# LM-008.net
KiCad netlist of a schematic drawn in Altium Designer
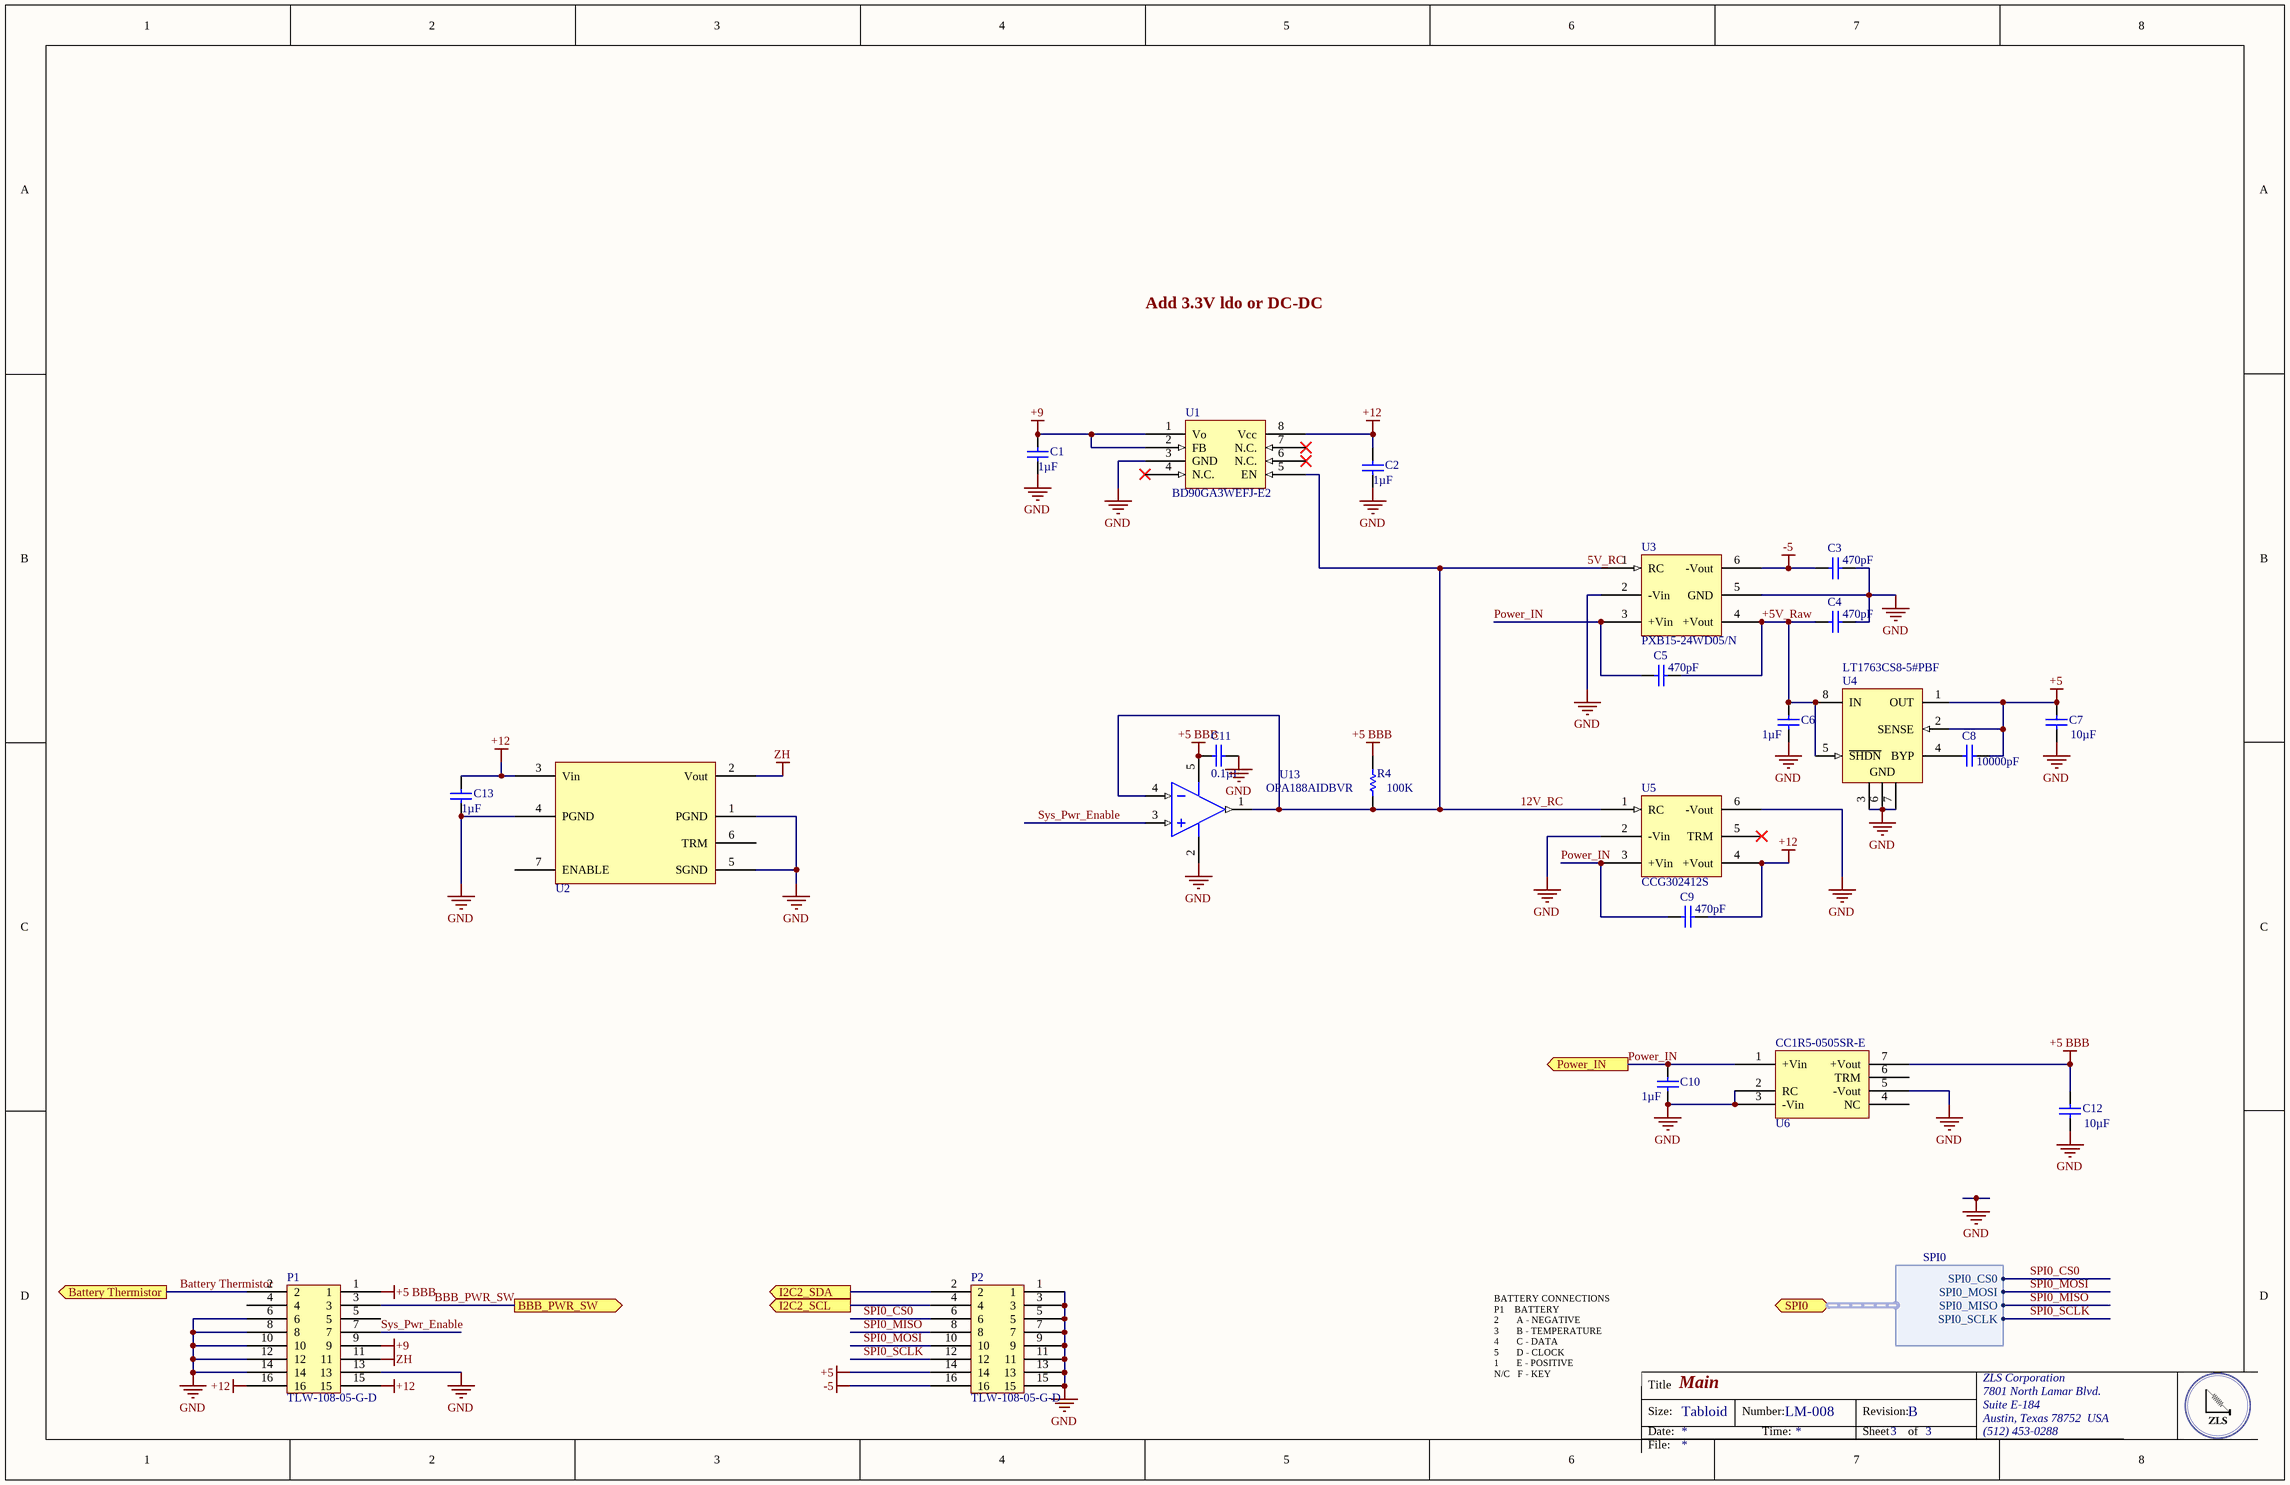
[diagram p0: LM-008.SchDoc]

(export (version "E")
  (design (tool "Eeschema 10.0.6"))
  (components
    (comp (ref "C1")
      (value "CAP CER 1UF 50V X7R 1210")
      (footprint "CAPC1206(3216)130_N")
      (fields
        (field (name "MANUFACTURER") "Murata Electronics North America")
        (field (name "MANUFACTURER PART NUMBER") "GRM32RR71H105KA01L")
        (field (name "CAPACITANCE") "1µF")
        (field (name "TOLERANCE") "±10%")
      )
      (libsource (lib "Altium Content Vault") (part "CMP-1037-04913-1"))
    )
    (comp (ref "C2")
      (value "CAP CER 1UF 50V X7R 1210")
      (footprint "CAPC1206(3216)130_N")
      (fields
        (field (name "MANUFACTURER") "Murata Electronics North America")
        (field (name "MANUFACTURER PART NUMBER") "GRM32RR71H105KA01L")
        (field (name "CAPACITANCE") "1µF")
        (field (name "TOLERANCE") "±10%")
      )
      (libsource (lib "Altium Content Vault") (part "CMP-1037-04913-1"))
    )
    (comp (ref "C3")
      (value "CAP CER 470PF 3KV X7R 1812")
      (footprint "CAPC1812(4532)230_M")
      (fields
        (field (name "MANUFACTURER") "Kemet")
        (field (name "MANUFACTURER PART NUMBER") "C1812C471KHRACTU")
        (field (name "CAPACITANCE") "470pF")
        (field (name "TOLERANCE") "10%")
      )
      (libsource (lib "Altium Content Vault") (part "CMP-1040-00561-1"))
    )
    (comp (ref "C4")
      (value "CAP CER 470PF 3KV X7R 1812")
      (footprint "CAPC1812(4532)230_M")
      (fields
        (field (name "MANUFACTURER") "Kemet")
        (field (name "MANUFACTURER PART NUMBER") "C1812C471KHRACTU")
        (field (name "CAPACITANCE") "470pF")
        (field (name "TOLERANCE") "10%")
      )
      (libsource (lib "Altium Content Vault") (part "CMP-1040-00561-1"))
    )
    (comp (ref "C5")
      (value "CAP CER 470PF 3KV X7R 1812")
      (footprint "CAPC1812(4532)230_M")
      (fields
        (field (name "MANUFACTURER") "Kemet")
        (field (name "MANUFACTURER PART NUMBER") "C1812C471KHRACTU")
        (field (name "CAPACITANCE") "470pF")
        (field (name "TOLERANCE") "10%")
      )
      (libsource (lib "Altium Content Vault") (part "CMP-1040-00561-1"))
    )
    (comp (ref "C6")
      (value "CAP CER 1UF 50V X7R 1210")
      (footprint "CAPC1210(3225)100_L")
      (fields
        (field (name "MANUFACTURER") "Murata Electronics North America")
        (field (name "MANUFACTURER PART NUMBER") "GRM32RR71H105KA01L")
        (field (name "CAPACITANCE") "1µF")
        (field (name "TOLERANCE") "±10%")
      )
      (libsource (lib "Altium Content Vault") (part "CMP-1038-00632-1"))
    )
    (comp (ref "C7")
      (value "CAP CER 10UF 10V X7R 0805")
      (footprint "CAPC0805(2012)145_N")
      (fields
        (field (name "MANUFACTURER") "Murata Electronics North America")
        (field (name "MANUFACTURER PART NUMBER") "GCM21BR71A106KE22L")
        (field (name "CAPACITANCE") "10µF")
        (field (name "TOLERANCE") "±10%")
      )
      (libsource (lib "Altium Content Vault") (part "CMP-1036-04795-1"))
    )
    (comp (ref "C8")
      (value "CAP CER 10000PF 25V X7R 0805")
      (footprint "CAPC0805(2012)145_N")
      (fields
        (field (name "MANUFACTURER") "Murata Electronics North America")
        (field (name "MANUFACTURER PART NUMBER") "GRM216R71E103KA01D")
        (field (name "CAPACITANCE") "10000pF")
        (field (name "TOLERANCE") "±10%")
      )
      (libsource (lib "Altium Content Vault") (part "CMP-1036-04795-1"))
    )
    (comp (ref "C9")
      (value "CAP CER 470PF 3KV X7R 1812")
      (footprint "CAPC1812(4532)230_M")
      (fields
        (field (name "MANUFACTURER") "Kemet")
        (field (name "MANUFACTURER PART NUMBER") "C1812C471KHRACTU")
        (field (name "CAPACITANCE") "470pF")
        (field (name "TOLERANCE") "10%")
      )
      (libsource (lib "Altium Content Vault") (part "CMP-1040-00561-1"))
    )
    (comp (ref "C10")
      (value "CAP CER 1UF 50V X7R 1210")
      (footprint "CAPC1210(3225)100_L")
      (fields
        (field (name "MANUFACTURER") "Murata Electronics North America")
        (field (name "MANUFACTURER PART NUMBER") "GRM32RR71H105KA01L")
        (field (name "CAPACITANCE") "1µF")
        (field (name "TOLERANCE") "±10%")
      )
      (libsource (lib "Altium Content Vault") (part "CMP-1038-00632-1"))
    )
    (comp (ref "C11")
      (value "CAP CER 0.1UF 16V X7R 0805")
      (footprint "CAPC0805(2012)145_N")
      (fields
        (field (name "TOLERANCE") "±10%")
        (field (name "MANUFACTURER") "Murata Electronics North America")
        (field (name "MANUFACTURER PART NUMBER") "GRM219R71C104KA01D")
        (field (name "CAPACITANCE") "0.1µF")
      )
      (libsource (lib "Altium Content Vault") (part "CMP-1036-04795-1"))
    )
    (comp (ref "C12")
      (value "CAP CER 10UF 10V X7R 0805")
      (footprint "CAPC0805(2012)145_N")
      (fields
        (field (name "MANUFACTURER") "Murata Electronics North America")
        (field (name "MANUFACTURER PART NUMBER") "GCM21BR71A106KE22L")
        (field (name "CAPACITANCE") "10µF")
        (field (name "TOLERANCE") "±10%")
      )
      (libsource (lib "Altium Content Vault") (part "CMP-1036-04795-1"))
    )
    (comp (ref "C13")
      (value "CAP CER 1UF 16V X7R 0805")
      (footprint "CAPC0805(2012)145_N")
      (fields
        (field (name "MANUFACTURER") "Taiyo Yuden")
        (field (name "MANUFACTURER PART NUMBER") "EMK212B7105KG-T")
        (field (name "CAPACITANCE") "1µF")
        (field (name "TOLERANCE") "±10%")
      )
      (libsource (lib "Altium Content Vault") (part "CMP-1036-04795-1"))
    )
    (comp (ref "P1")
      (value "TLW-108-05-G-D")
      (footprint "TLW-108-05-G-D")
      (description "CONN HEADER .100\" 16POS DL GOLD")
      (fields
        (field (name "MANUFACTURER") "Samtec Inc.")
        (field (name "MANUFACTURER PART NUMBER") "TLW-108-05-G-D")
      )
      (libsource (lib "ZLS_Schematic_lib") (part "TLW-108-05-G-D"))
    )
    (comp (ref "P2")
      (value "TLW-108-05-G-D")
      (footprint "TLW-108-05-G-D")
      (description "CONN HEADER .100\" 16POS DL GOLD")
      (fields
        (field (name "MANUFACTURER") "Samtec Inc.")
        (field (name "MANUFACTURER PART NUMBER") "TLW-108-05-G-D")
      )
      (libsource (lib "ZLS_Schematic_lib") (part "TLW-108-05-G-D"))
    )
    (comp (ref "R4")
      (value "100K")
      (footprint "RESC0402(1005)_L")
      (fields (field (name "TOLERANCE") "±1%"))
      (libsource (lib "Altium Content Vault") (part "CMP-1011-00927-1"))
    )
    (comp (ref "U1")
      (value "BD90GA3WEFJ-E2")
      (footprint "TSOP127P600X100-8N")
      (description "IC REG LDO 9V 0.3A 8HTSOP-J")
      (fields
        (field (name "MANUFACTURER") "Rohm Semiconductor")
        (field (name "MANUFACTURER PART NUMBER") "BD90GA3WEFJ-E2")
      )
      (libsource (lib "ZLS_Schematic_lib") (part "BD90GA3WEFJ-E2"))
    )
    (comp (ref "U2")
      (value "ABXS002A3X41-SRZ")
      (footprint "ABXS002A3X41-SRZ")
      (libsource (lib "ZLS_Schematic_lib") (part "ABXS002A3X41-SRZ"))
    )
    (comp (ref "U3")
      (value "PXB15-24WD05/N")
      (footprint "PXB15-24WD05/N")
      (description "IC CONV DC-DC 15W DUAL 5V PCB")
      (libsource (lib "ZLS_LIB") (part "CCG302412S"))
    )
    (comp (ref "U4")
      (value "LT1763CS8-5#PBF")
      (footprint "LT-S8-8_M")
      (fields (field (name "MANUFACTURER") "Linear Technology"))
      (libsource (lib "Altium Content Vault") (part "LT-LT1763-S8-8"))
    )
    (comp (ref "U5")
      (value "CCG302412S")
      (footprint "CCG30")
      (description "DC/DC CONVERTER 12V 2.5A PCB")
      (libsource (lib "") (part "CCG302412S_1"))
    )
    (comp (ref "U6")
      (value "CC1R5-0505SR-E")
      (footprint "CC1R5-0505SR-E")
      (description "CONV DC/DC 1.5W SNGL 5V 5V SMD")
      (fields
        (field (name "MANUFACTURER") "TDK-Lambda Americas Inc.")
        (field (name "MANUFACTURER PART NUMBER") "CC1R5-0505SR-E")
      )
      (libsource (lib "ZLS_Schematic_lib") (part "CC1R5-0505SR-E"))
    )
    (comp (ref "U13")
      (value "OPA188AIDBVR")
      (footprint "DBV0005A_M")
      (fields (field (name "MANUFACTURER") "Texas Instruments"))
      (libsource (lib "Altium Content Vault") (part "CMP-0809-00005-2"))
    )
  )
  (nets
    (net (code "2") (name "+5") (class "Default")
      (node (ref "C7") (pin "2") (pinfunction "2_2") (pintype "passive"))
      (node (ref "C8") (pin "1") (pinfunction "1_1") (pintype "passive"))
      (node (ref "P2") (pin "14") (pinfunction "14_14") (pintype "passive"))
      (node (ref "U4") (pin "1") (pinfunction "OUT_1") (pintype "power_in"))
      (node (ref "U4") (pin "2") (pinfunction "SENSE_2") (pintype "input"))
    )
    (net (code "3") (name "+5 BBB") (class "Default")
      (node (ref "C11") (pin "1") (pinfunction "1_1") (pintype "passive"))
      (node (ref "C12") (pin "2") (pinfunction "2_2") (pintype "passive"))
      (node (ref "P1") (pin "1") (pinfunction "1_1") (pintype "passive"))
      (node (ref "R4") (pin "2") (pinfunction "2_2") (pintype "passive"))
      (node (ref "U13") (pin "5") (pinfunction "V+_5") (pintype "power_in"))
      (node (ref "U6") (pin "7") (pinfunction "+Vout_7") (pintype "passive"))
    )
    (net (code "4") (name "+9") (class "Default")
      (node (ref "C1") (pin "2") (pinfunction "2_2") (pintype "passive"))
      (node (ref "P1") (pin "9") (pinfunction "9_9") (pintype "passive"))
      (node (ref "U1") (pin "1") (pinfunction "Vo_1") (pintype "power_in"))
      (node (ref "U1") (pin "2") (pinfunction "FB_2") (pintype "input"))
    )
    (net (code "5") (name "+12") (class "Default")
      (node (ref "C13") (pin "2") (pinfunction "2_2") (pintype "passive"))
      (node (ref "C2") (pin "2") (pinfunction "2_2") (pintype "passive"))
      (node (ref "C9") (pin "2") (pinfunction "2_2") (pintype "passive"))
      (node (ref "P1") (pin "15") (pinfunction "15_15") (pintype "passive"))
      (node (ref "P1") (pin "16") (pinfunction "16_16") (pintype "passive"))
      (node (ref "U1") (pin "8") (pinfunction "Vcc_8") (pintype "power_in"))
      (node (ref "U2") (pin "3") (pinfunction "Vin_3") (pintype "passive"))
      (node (ref "U5") (pin "4") (pinfunction "+Vout_4") (pintype "power_in"))
    )
    (net (code "6") (name "-5") (class "Default")
      (node (ref "C3") (pin "1") (pinfunction "1_1") (pintype "passive"))
      (node (ref "P2") (pin "16") (pinfunction "16_16") (pintype "passive"))
      (node (ref "U3") (pin "6") (pinfunction "-Vout_6") (pintype "power_in"))
    )
    (net (code "7") (name "/+5V_Raw") (class "Default")
      (node (ref "C4") (pin "1") (pinfunction "1_1") (pintype "passive"))
      (node (ref "C5") (pin "2") (pinfunction "2_2") (pintype "passive"))
      (node (ref "C6") (pin "2") (pinfunction "2_2") (pintype "passive"))
      (node (ref "U3") (pin "4") (pinfunction "+Vout_4") (pintype "power_in"))
      (node (ref "U4") (pin "5") (pinfunction "~{SHDN}_5") (pintype "input"))
      (node (ref "U4") (pin "8") (pinfunction "IN_8") (pintype "power_in"))
    )
    (net (code "8") (name "/12V_RC") (class "Default")
      (node (ref "R4") (pin "1") (pinfunction "1_1") (pintype "passive"))
      (node (ref "U1") (pin "5") (pinfunction "EN_5") (pintype "input"))
      (node (ref "U13") (pin "1") (pinfunction "OUT_1") (pintype "output"))
      (node (ref "U13") (pin "4") (pinfunction "IN-_4") (pintype "input"))
      (node (ref "U3") (pin "1") (pinfunction "RC_1") (pintype "input"))
      (node (ref "U5") (pin "1") (pinfunction "RC_1") (pintype "input"))
    )
    (net (code "9") (name "/BBB_PWR_SW") (class "Default")
      (node (ref "P1") (pin "3") (pinfunction "3_3") (pintype "passive"))
    )
    (net (code "10") (name "/Battery Thermistor") (class "Default")
      (node (ref "P1") (pin "2") (pinfunction "2_2") (pintype "passive"))
    )
    (net (code "11") (name "/I2C2_SCL") (class "Default")
      (node (ref "P2") (pin "4") (pinfunction "4_4") (pintype "passive"))
    )
    (net (code "12") (name "/I2C2_SDA") (class "Default")
      (node (ref "P2") (pin "2") (pinfunction "2_2") (pintype "passive"))
    )
    (net (code "13") (name "/Power_IN") (class "Default")
      (node (ref "C10") (pin "2") (pinfunction "2_2") (pintype "passive"))
      (node (ref "C5") (pin "1") (pinfunction "1_1") (pintype "passive"))
      (node (ref "C9") (pin "1") (pinfunction "1_1") (pintype "passive"))
      (node (ref "U3") (pin "3") (pinfunction "+Vin_3") (pintype "power_in"))
      (node (ref "U5") (pin "3") (pinfunction "+Vin_3") (pintype "passive"))
      (node (ref "U6") (pin "1") (pinfunction "+Vin_1") (pintype "passive"))
    )
    (net (code "14") (name "/SPI0_CS0") (class "Default")
      (node (ref "P2") (pin "6") (pinfunction "6_6") (pintype "passive"))
    )
    (net (code "15") (name "/SPI0_MISO") (class "Default")
      (node (ref "P2") (pin "8") (pinfunction "8_8") (pintype "passive"))
    )
    (net (code "16") (name "/SPI0_MOSI") (class "Default")
      (node (ref "P2") (pin "10") (pinfunction "10_10") (pintype "passive"))
    )
    (net (code "17") (name "/SPI0_SCLK") (class "Default")
      (node (ref "P2") (pin "12") (pinfunction "12_12") (pintype "passive"))
    )
    (net (code "18") (name "/Sys_Pwr_Enable") (class "Default")
      (node (ref "P1") (pin "7") (pinfunction "7_7") (pintype "passive"))
      (node (ref "U13") (pin "3") (pinfunction "IN+_3") (pintype "input"))
    )
    (net (code "20") (name "GND") (class "Default")
      (node (ref "C1") (pin "1") (pinfunction "1_1") (pintype "passive"))
      (node (ref "C10") (pin "1") (pinfunction "1_1") (pintype "passive"))
      (node (ref "C11") (pin "2") (pinfunction "2_2") (pintype "passive"))
      (node (ref "C12") (pin "1") (pinfunction "1_1") (pintype "passive"))
      (node (ref "C13") (pin "1") (pinfunction "1_1") (pintype "passive"))
      (node (ref "C2") (pin "1") (pinfunction "1_1") (pintype "passive"))
      (node (ref "C3") (pin "2") (pinfunction "2_2") (pintype "passive"))
      (node (ref "C4") (pin "2") (pinfunction "2_2") (pintype "passive"))
      (node (ref "C6") (pin "1") (pinfunction "1_1") (pintype "passive"))
      (node (ref "C7") (pin "1") (pinfunction "1_1") (pintype "passive"))
      (node (ref "P1") (pin "10") (pinfunction "10_10") (pintype "passive"))
      (node (ref "P1") (pin "12") (pinfunction "12_12") (pintype "passive"))
      (node (ref "P1") (pin "13") (pinfunction "13_13") (pintype "passive"))
      (node (ref "P1") (pin "14") (pinfunction "14_14") (pintype "passive"))
      (node (ref "P1") (pin "6") (pinfunction "6_6") (pintype "passive"))
      (node (ref "P1") (pin "8") (pinfunction "8_8") (pintype "passive"))
      (node (ref "P2") (pin "1") (pinfunction "1_1") (pintype "passive"))
      (node (ref "P2") (pin "11") (pinfunction "11_11") (pintype "passive"))
      (node (ref "P2") (pin "13") (pinfunction "13_13") (pintype "passive"))
      (node (ref "P2") (pin "15") (pinfunction "15_15") (pintype "passive"))
      (node (ref "P2") (pin "3") (pinfunction "3_3") (pintype "passive"))
      (node (ref "P2") (pin "5") (pinfunction "5_5") (pintype "passive"))
      (node (ref "P2") (pin "7") (pinfunction "7_7") (pintype "passive"))
      (node (ref "P2") (pin "9") (pinfunction "9_9") (pintype "passive"))
      (node (ref "U1") (pin "3") (pinfunction "GND_3") (pintype "power_in"))
      (node (ref "U13") (pin "2") (pinfunction "V-_2") (pintype "power_in"))
      (node (ref "U2") (pin "1") (pinfunction "PGND_1") (pintype "passive"))
      (node (ref "U2") (pin "4") (pinfunction "PGND_4") (pintype "passive"))
      (node (ref "U2") (pin "5") (pinfunction "SGND_5") (pintype "passive"))
      (node (ref "U3") (pin "2") (pinfunction "-Vin_2") (pintype "power_in"))
      (node (ref "U3") (pin "5") (pinfunction "GND_5") (pintype "power_in"))
      (node (ref "U4") (pin "3") (pinfunction "GND_3") (pintype "power_in"))
      (node (ref "U4") (pin "6") (pinfunction "GND_6") (pintype "power_in"))
      (node (ref "U4") (pin "7") (pinfunction "GND_7") (pintype "power_in"))
      (node (ref "U5") (pin "2") (pinfunction "-Vin_2") (pintype "power_in"))
      (node (ref "U5") (pin "6") (pinfunction "-Vout_6") (pintype "power_in"))
      (node (ref "U6") (pin "2") (pinfunction "RC_2") (pintype "passive"))
      (node (ref "U6") (pin "3") (pinfunction "-Vin_3") (pintype "passive"))
      (node (ref "U6") (pin "5") (pinfunction "-Vout_5") (pintype "passive"))
    )
    (net (code "21") (name "Net-(U4-BYP)") (class "Default")
      (node (ref "C8") (pin "2") (pinfunction "2_2") (pintype "passive"))
      (node (ref "U4") (pin "4") (pinfunction "BYP_4") (pintype "passive"))
    )
    (net (code "22") (name "ZH") (class "Default")
      (node (ref "P1") (pin "11") (pinfunction "11_11") (pintype "passive"))
      (node (ref "U2") (pin "2") (pinfunction "Vout_2") (pintype "passive"))
    )
    (net (code "23") (name "unconnected-(P1-Pad4)") (class "Default")
      (node (ref "P1") (pin "4") (pinfunction "4_4") (pintype "passive"))
    )
    (net (code "24") (name "unconnected-(P1-Pad5)") (class "Default")
      (node (ref "P1") (pin "5") (pinfunction "5_5") (pintype "passive"))
    )
    (net (code "25") (name "unconnected-(U1-N.C.-Pad4)") (class "Default")
      (node (ref "U1") (pin "4") (pinfunction "N.C._4") (pintype "input+no_connect"))
    )
    (net (code "26") (name "unconnected-(U1-N.C.-Pad6)") (class "Default")
      (node (ref "U1") (pin "6") (pinfunction "N.C._6") (pintype "input+no_connect"))
    )
    (net (code "27") (name "unconnected-(U1-N.C.-Pad7)") (class "Default")
      (node (ref "U1") (pin "7") (pinfunction "N.C._7") (pintype "input+no_connect"))
    )
    (net (code "28") (name "unconnected-(U2-ENABLE-Pad7)") (class "Default")
      (node (ref "U2") (pin "7") (pinfunction "ENABLE_7") (pintype "passive"))
    )
    (net (code "29") (name "unconnected-(U2-TRM-Pad6)") (class "Default")
      (node (ref "U2") (pin "6") (pinfunction "TRM_6") (pintype "passive"))
    )
    (net (code "30") (name "unconnected-(U5-TRM-Pad5)") (class "Default")
      (node (ref "U5") (pin "5") (pinfunction "TRM_5") (pintype "passive+no_connect"))
    )
    (net (code "31") (name "unconnected-(U6-NC-Pad4)") (class "Default")
      (node (ref "U6") (pin "4") (pinfunction "NC_4") (pintype "passive"))
    )
    (net (code "32") (name "unconnected-(U6-TRM-Pad6)") (class "Default")
      (node (ref "U6") (pin "6") (pinfunction "TRM_6") (pintype "passive"))
    )
  )
)
